# PCB-CMB-2.net
KiCad netlist of a schematic drawn in EAGLE
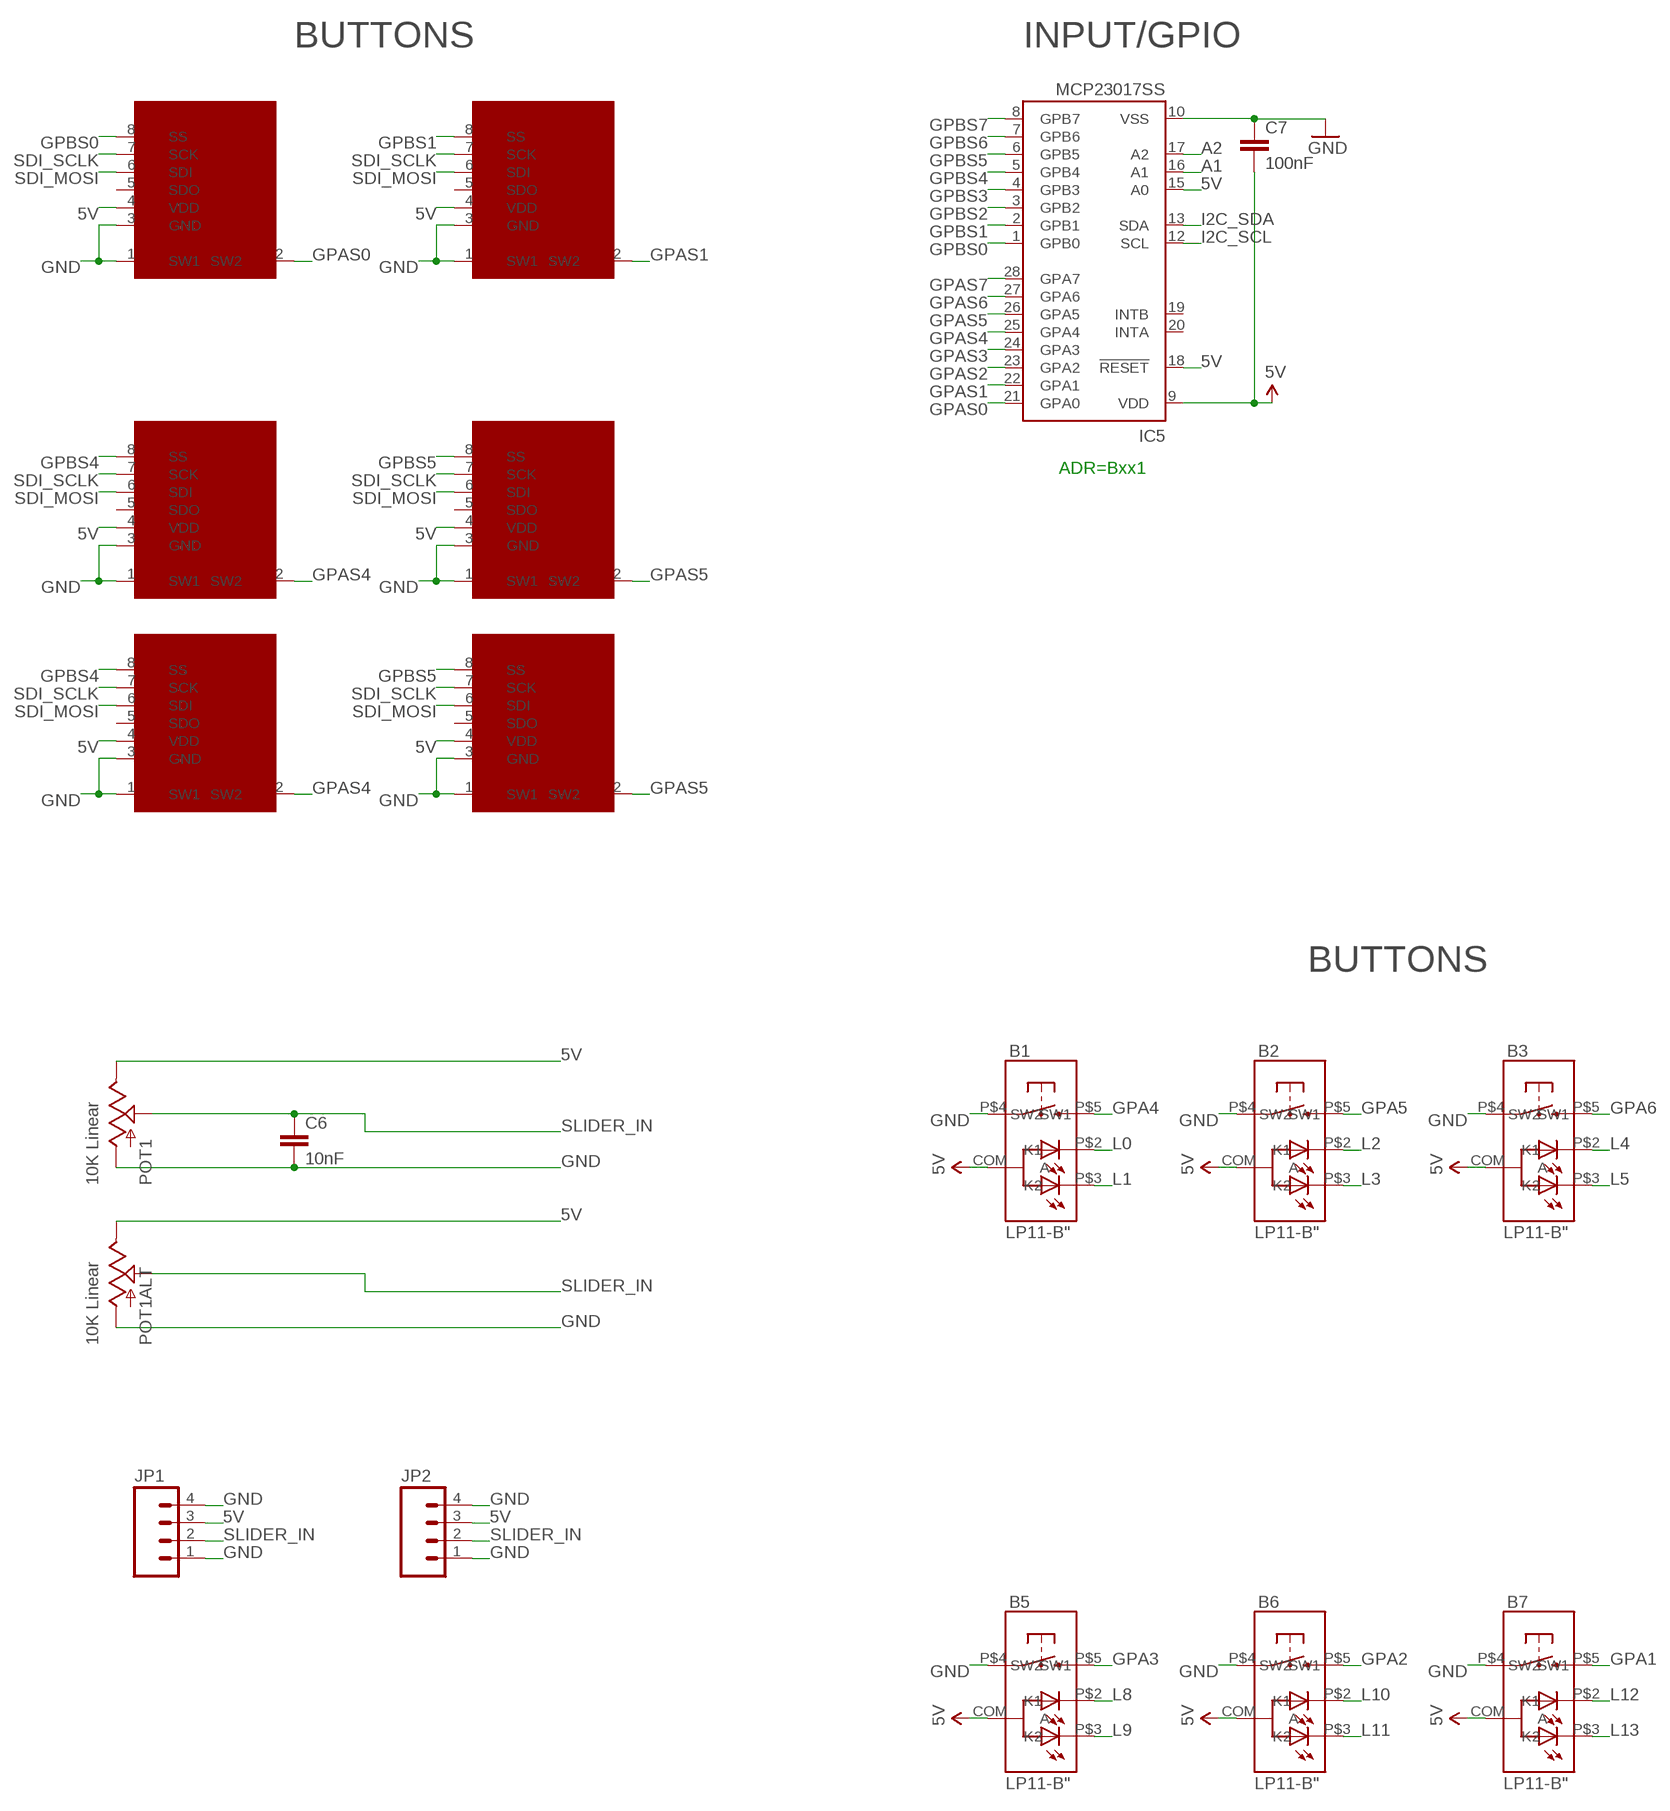
[diagram p0: schematic, sheet 1, part 1 of 2]
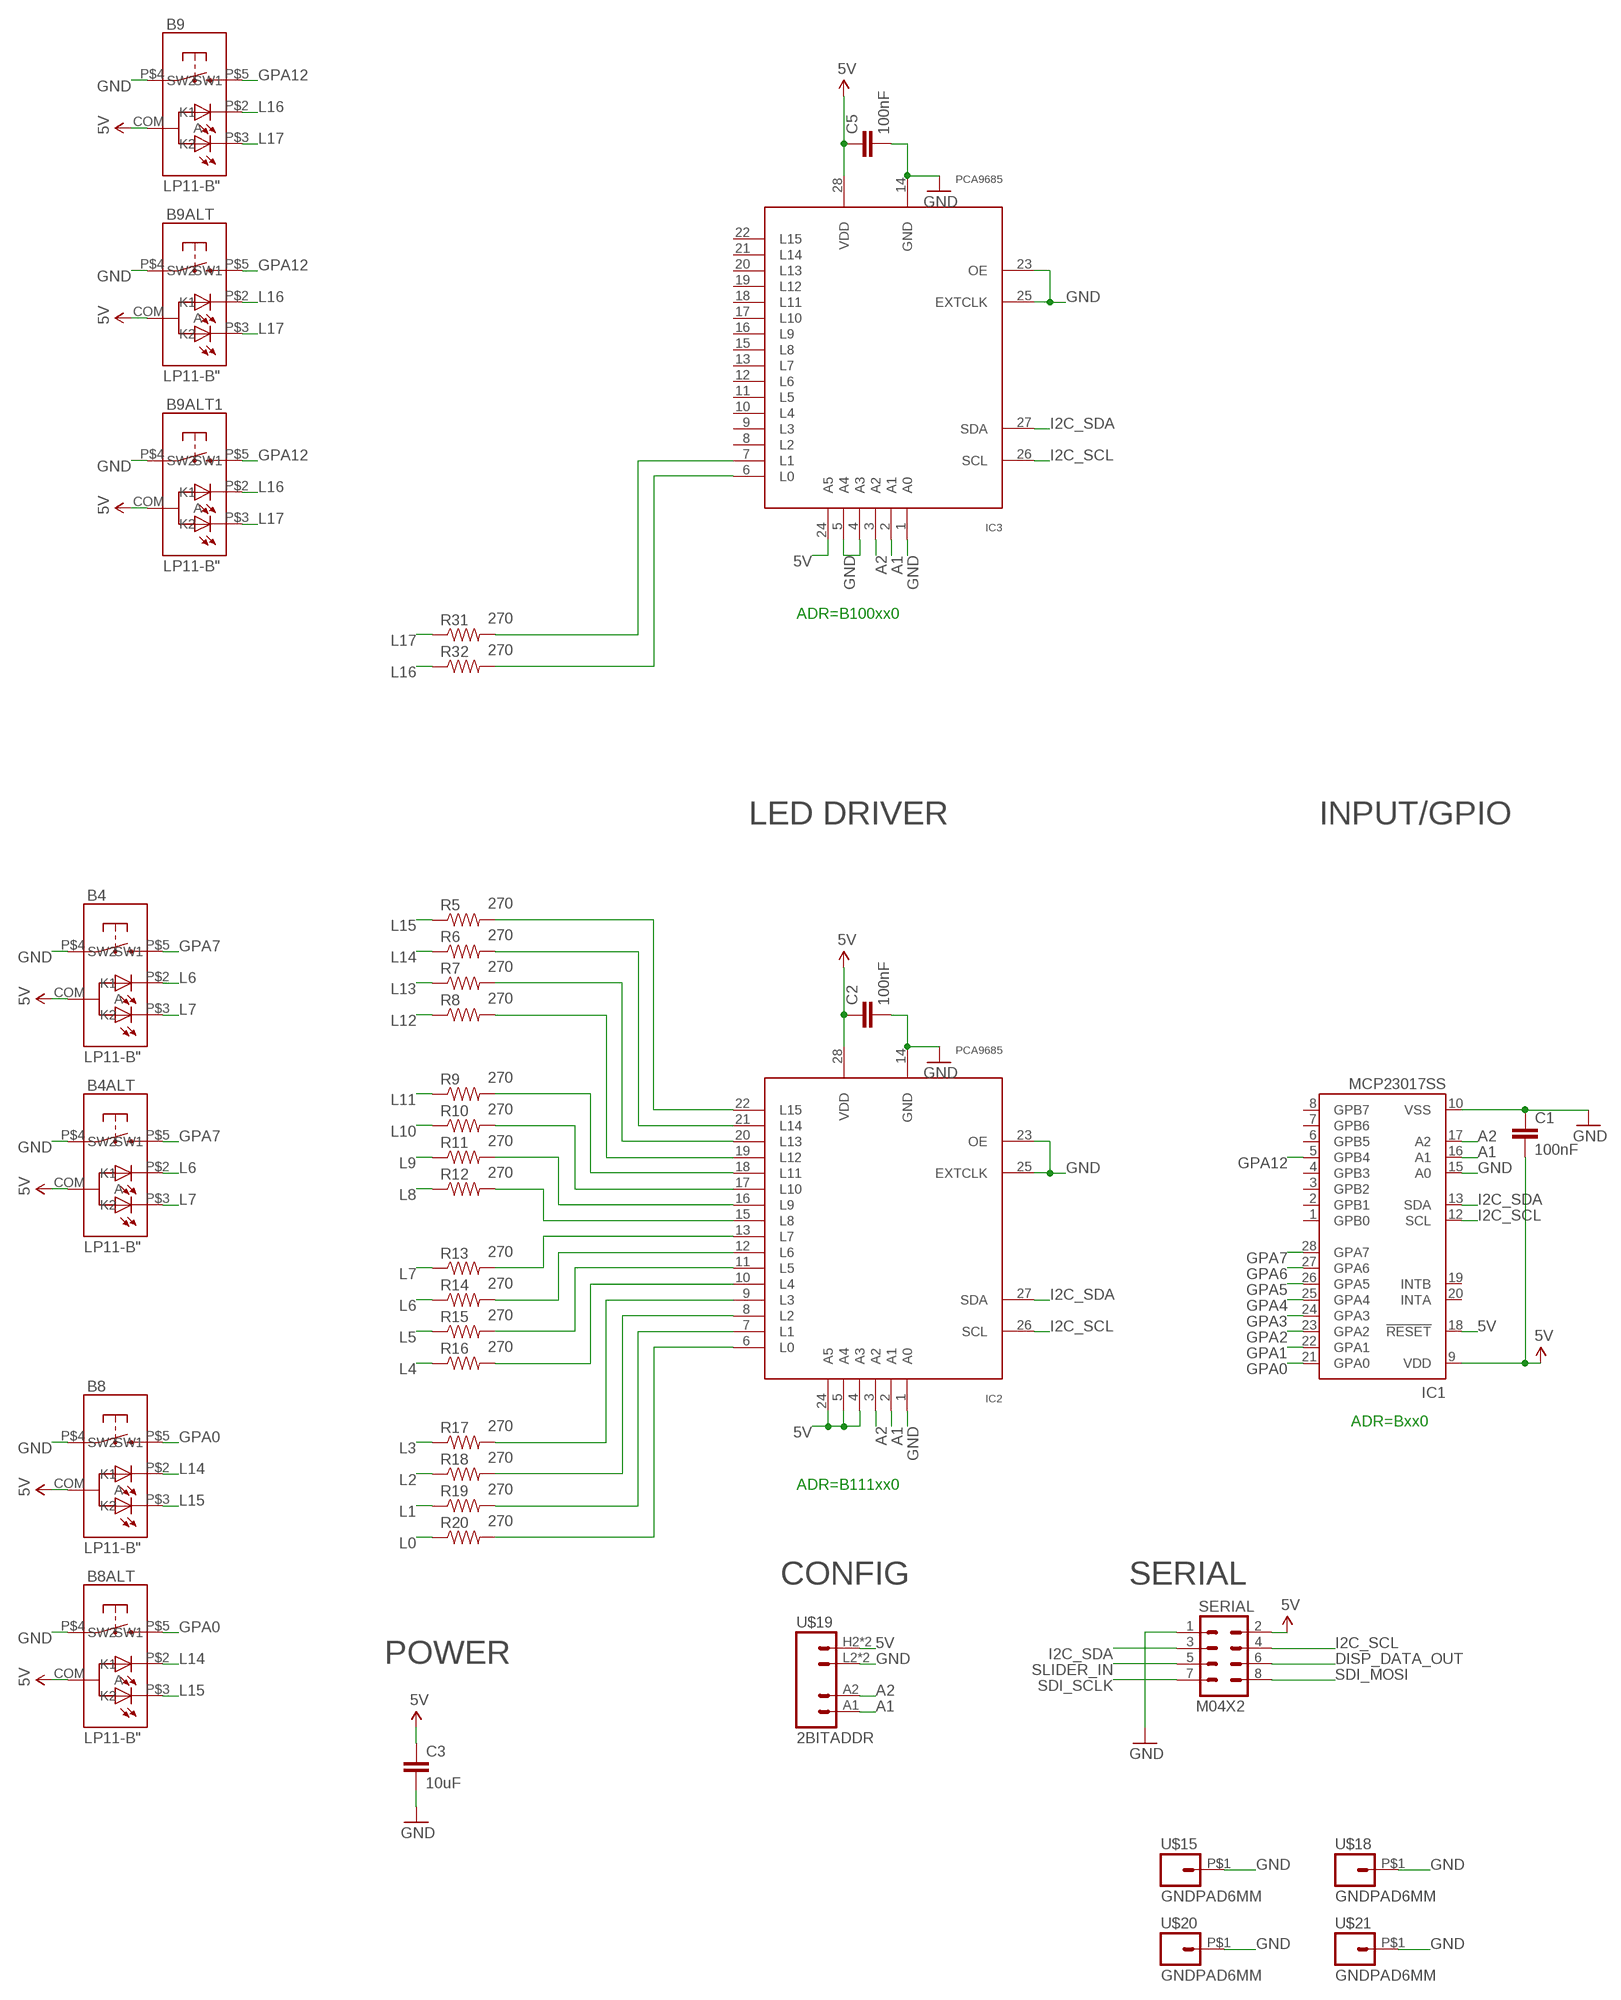
[diagram p1: schematic, sheet 1, part 2 of 2]

(export (version "E")
  (design (tool "Eeschema 10.0.6"))
  (components
    (comp (ref "B1")
      (value "LP11-B\"")
      (footprint "eagle-import:LP11")
      (libsource (lib "eagle-import") (part "LP11-B{dblquote}"))
    )
    (comp (ref "B2")
      (value "LP11-B\"")
      (footprint "eagle-import:LP11")
      (libsource (lib "eagle-import") (part "LP11-B{dblquote}"))
    )
    (comp (ref "B3")
      (value "LP11-B\"")
      (footprint "eagle-import:LP11")
      (libsource (lib "eagle-import") (part "LP11-B{dblquote}"))
    )
    (comp (ref "B4")
      (value "LP11-B\"")
      (footprint "eagle-import:LP11")
      (libsource (lib "eagle-import") (part "LP11-B{dblquote}"))
    )
    (comp (ref "B4ALT")
      (value "LP11-B\"")
      (footprint "eagle-import:LP11")
      (libsource (lib "eagle-import") (part "LP11-B{dblquote}"))
    )
    (comp (ref "B5")
      (value "LP11-B\"")
      (footprint "eagle-import:LP11")
      (libsource (lib "eagle-import") (part "LP11-B{dblquote}"))
    )
    (comp (ref "B6")
      (value "LP11-B\"")
      (footprint "eagle-import:LP11")
      (libsource (lib "eagle-import") (part "LP11-B{dblquote}"))
    )
    (comp (ref "B7")
      (value "LP11-B\"")
      (footprint "eagle-import:LP11")
      (libsource (lib "eagle-import") (part "LP11-B{dblquote}"))
    )
    (comp (ref "B8")
      (value "LP11-B\"")
      (footprint "eagle-import:LP11")
      (libsource (lib "eagle-import") (part "LP11-B{dblquote}"))
    )
    (comp (ref "B8ALT")
      (value "LP11-B\"")
      (footprint "eagle-import:LP11")
      (libsource (lib "eagle-import") (part "LP11-B{dblquote}"))
    )
    (comp (ref "B9")
      (value "LP11-B\"")
      (footprint "eagle-import:LP11")
      (libsource (lib "eagle-import") (part "LP11-B{dblquote}"))
    )
    (comp (ref "B9ALT")
      (value "LP11-B\"")
      (footprint "eagle-import:LP11")
      (libsource (lib "eagle-import") (part "LP11-B{dblquote}"))
    )
    (comp (ref "B9ALT1")
      (value "LP11-B\"")
      (footprint "eagle-import:LP11")
      (libsource (lib "eagle-import") (part "LP11-B{dblquote}"))
    )
    (comp (ref "C1")
      (value "100nF")
      (footprint "eagle-import:0603-CAP")
      (libsource (lib "eagle-import") (part "CAP0603-CAP"))
    )
    (comp (ref "C2")
      (value "100nF")
      (footprint "eagle-import:0603-CAP")
      (libsource (lib "eagle-import") (part "CAP0603-CAP"))
    )
    (comp (ref "C3")
      (value "10uF")
      (footprint "eagle-import:0805")
      (libsource (lib "eagle-import") (part "CAP0805"))
    )
    (comp (ref "C5")
      (value "100nF")
      (footprint "eagle-import:0603-CAP")
      (libsource (lib "eagle-import") (part "CAP0603-CAP"))
    )
    (comp (ref "C6")
      (value "10nF")
      (footprint "eagle-import:0603-CAP")
      (libsource (lib "eagle-import") (part "CAP0603-CAP"))
    )
    (comp (ref "C7")
      (value "100nF")
      (footprint "eagle-import:0603-CAP")
      (libsource (lib "eagle-import") (part "CAP0603-CAP"))
    )
    (comp (ref "IC1")
      (value "MCP23017SS")
      (footprint "eagle-import:SSOP28")
      (fields
        (field (name "MF") "MICROCHIP")
        (field (name "MPN") "MCP23017-E/SS")
        (field (name "MPN_1") "MCP23017-E/SS")
        (field (name "OC_FARNELL") "1467674")
        (field (name "OC_NEWARK") "31K2960")
      )
      (libsource (lib "eagle-import") (part "MCP23017SS"))
    )
    (comp (ref "IC2")
      (value "PCA9685")
      (footprint "eagle-import:TSSOP28")
      (libsource (lib "eagle-import") (part "PCA9685"))
    )
    (comp (ref "IC3")
      (value "PCA9685")
      (footprint "eagle-import:TSSOP28")
      (libsource (lib "eagle-import") (part "PCA9685"))
    )
    (comp (ref "IC5")
      (value "MCP23017SS")
      (footprint "eagle-import:SSOP28")
      (fields
        (field (name "MF") "MICROCHIP")
        (field (name "MPN") "MCP23017-E/SS")
        (field (name "MPN_1") "MCP23017-E/SS")
        (field (name "OC_FARNELL") "1467674")
        (field (name "OC_NEWARK") "31K2960")
      )
      (libsource (lib "eagle-import") (part "MCP23017SS"))
    )
    (comp (ref "JP1")
      (value "M04PTH")
      (footprint "eagle-import:1X04")
      (libsource (lib "eagle-import") (part "M04PTH"))
    )
    (comp (ref "JP2")
      (value "M04PTH")
      (footprint "eagle-import:1X04")
      (libsource (lib "eagle-import") (part "M04PTH"))
    )
    (comp (ref "POT1")
      (value "10K Linear")
      (footprint "eagle-import:SLIDER20")
      (libsource (lib "eagle-import") (part "SLIDER20"))
    )
    (comp (ref "POT1ALT")
      (value "10K Linear")
      (footprint "eagle-import:SLIDER20")
      (libsource (lib "eagle-import") (part "SLIDER20"))
    )
    (comp (ref "R5")
      (value "270")
      (footprint "eagle-import:0603-RES")
      (libsource (lib "eagle-import") (part "RESISTOR0603-RES"))
    )
    (comp (ref "R6")
      (value "270")
      (footprint "eagle-import:0603-RES")
      (libsource (lib "eagle-import") (part "RESISTOR0603-RES"))
    )
    (comp (ref "R7")
      (value "270")
      (footprint "eagle-import:0603-RES")
      (libsource (lib "eagle-import") (part "RESISTOR0603-RES"))
    )
    (comp (ref "R8")
      (value "270")
      (footprint "eagle-import:0603-RES")
      (libsource (lib "eagle-import") (part "RESISTOR0603-RES"))
    )
    (comp (ref "R9")
      (value "270")
      (footprint "eagle-import:0603-RES")
      (libsource (lib "eagle-import") (part "RESISTOR0603-RES"))
    )
    (comp (ref "R10")
      (value "270")
      (footprint "eagle-import:0603-RES")
      (libsource (lib "eagle-import") (part "RESISTOR0603-RES"))
    )
    (comp (ref "R11")
      (value "270")
      (footprint "eagle-import:0603-RES")
      (libsource (lib "eagle-import") (part "RESISTOR0603-RES"))
    )
    (comp (ref "R12")
      (value "270")
      (footprint "eagle-import:0603-RES")
      (libsource (lib "eagle-import") (part "RESISTOR0603-RES"))
    )
    (comp (ref "R13")
      (value "270")
      (footprint "eagle-import:0603-RES")
      (libsource (lib "eagle-import") (part "RESISTOR0603-RES"))
    )
    (comp (ref "R14")
      (value "270")
      (footprint "eagle-import:0603-RES")
      (libsource (lib "eagle-import") (part "RESISTOR0603-RES"))
    )
    (comp (ref "R15")
      (value "270")
      (footprint "eagle-import:0603-RES")
      (libsource (lib "eagle-import") (part "RESISTOR0603-RES"))
    )
    (comp (ref "R16")
      (value "270")
      (footprint "eagle-import:0603-RES")
      (libsource (lib "eagle-import") (part "RESISTOR0603-RES"))
    )
    (comp (ref "R17")
      (value "270")
      (footprint "eagle-import:0603-RES")
      (libsource (lib "eagle-import") (part "RESISTOR0603-RES"))
    )
    (comp (ref "R18")
      (value "270")
      (footprint "eagle-import:0603-RES")
      (libsource (lib "eagle-import") (part "RESISTOR0603-RES"))
    )
    (comp (ref "R19")
      (value "270")
      (footprint "eagle-import:0603-RES")
      (libsource (lib "eagle-import") (part "RESISTOR0603-RES"))
    )
    (comp (ref "R20")
      (value "270")
      (footprint "eagle-import:0603-RES")
      (libsource (lib "eagle-import") (part "RESISTOR0603-RES"))
    )
    (comp (ref "R31")
      (value "270")
      (footprint "eagle-import:0603-RES")
      (libsource (lib "eagle-import") (part "RESISTOR0603-RES"))
    )
    (comp (ref "R32")
      (value "270")
      (footprint "eagle-import:0603-RES")
      (libsource (lib "eagle-import") (part "RESISTOR0603-RES"))
    )
    (comp (ref "SERIAL")
      (value "M04X2")
      (footprint "eagle-import:2X4")
      (libsource (lib "eagle-import") (part "M04X2"))
    )
    (comp (ref "SSW1")
      (value "SMART_SWITCHSMART_SWITCH_8PIN")
      (footprint "eagle-import:SMART_SWITCH")
      (libsource (lib "eagle-import") (part "SMART_SWITCHSMART_SWITCH_8PIN"))
    )
    (comp (ref "SSW2")
      (value "SMART_SWITCHSMART_SWITCH_8PIN")
      (footprint "eagle-import:SMART_SWITCH")
      (libsource (lib "eagle-import") (part "SMART_SWITCHSMART_SWITCH_8PIN"))
    )
    (comp (ref "SSW5")
      (value "SMART_SWITCHSMART_SWITCH_8PIN")
      (footprint "eagle-import:SMART_SWITCH")
      (libsource (lib "eagle-import") (part "SMART_SWITCHSMART_SWITCH_8PIN"))
    )
    (comp (ref "SSW5ALT")
      (value "SMART_SWITCHSMART_SWITCH_8PIN")
      (footprint "eagle-import:SMART_SWITCH")
      (libsource (lib "eagle-import") (part "SMART_SWITCHSMART_SWITCH_8PIN"))
    )
    (comp (ref "SSW6")
      (value "SMART_SWITCHSMART_SWITCH_8PIN")
      (footprint "eagle-import:SMART_SWITCH")
      (libsource (lib "eagle-import") (part "SMART_SWITCHSMART_SWITCH_8PIN"))
    )
    (comp (ref "SSW6ALT")
      (value "SMART_SWITCHSMART_SWITCH_8PIN")
      (footprint "eagle-import:SMART_SWITCH")
      (libsource (lib "eagle-import") (part "SMART_SWITCHSMART_SWITCH_8PIN"))
    )
    (comp (ref "U$15")
      (value "GNDPAD6MM")
      (footprint "eagle-import:3.2MMPAD6MM")
      (libsource (lib "eagle-import") (part "GNDPAD6MM"))
    )
    (comp (ref "U$18")
      (value "GNDPAD6MM")
      (footprint "eagle-import:3.2MMPAD6MM")
      (libsource (lib "eagle-import") (part "GNDPAD6MM"))
    )
    (comp (ref "U$19")
      (value "2BITADDR")
      (footprint "eagle-import:2BITADDR")
      (libsource (lib "eagle-import") (part "2BITADDR"))
    )
    (comp (ref "U$20")
      (value "GNDPAD6MM")
      (footprint "eagle-import:3.2MMPAD6MM")
      (libsource (lib "eagle-import") (part "GNDPAD6MM"))
    )
    (comp (ref "U$21")
      (value "GNDPAD6MM")
      (footprint "eagle-import:3.2MMPAD6MM")
      (libsource (lib "eagle-import") (part "GNDPAD6MM"))
    )
  )
  (nets
    (net (code "1") (name "5V") (class "Default")
      (node (ref "B1") (pin "COM") (pinfunction "A_COM") (pintype "bidirectional"))
      (node (ref "B2") (pin "COM") (pinfunction "A_COM") (pintype "bidirectional"))
      (node (ref "B3") (pin "COM") (pinfunction "A_COM") (pintype "bidirectional"))
      (node (ref "B4") (pin "COM") (pinfunction "A_COM") (pintype "bidirectional"))
      (node (ref "B4ALT") (pin "COM") (pinfunction "A_COM") (pintype "bidirectional"))
      (node (ref "B5") (pin "COM") (pinfunction "A_COM") (pintype "bidirectional"))
      (node (ref "B6") (pin "COM") (pinfunction "A_COM") (pintype "bidirectional"))
      (node (ref "B7") (pin "COM") (pinfunction "A_COM") (pintype "bidirectional"))
      (node (ref "B8") (pin "COM") (pinfunction "A_COM") (pintype "bidirectional"))
      (node (ref "B8ALT") (pin "COM") (pinfunction "A_COM") (pintype "bidirectional"))
      (node (ref "B9") (pin "COM") (pinfunction "A_COM") (pintype "bidirectional"))
      (node (ref "B9ALT") (pin "COM") (pinfunction "A_COM") (pintype "bidirectional"))
      (node (ref "B9ALT1") (pin "COM") (pinfunction "A_COM") (pintype "bidirectional"))
      (node (ref "C1") (pin "2") (pinfunction "2_2") (pintype "passive"))
      (node (ref "C2") (pin "1") (pinfunction "1_1") (pintype "passive"))
      (node (ref "C3") (pin "1") (pinfunction "1_1") (pintype "passive"))
      (node (ref "C5") (pin "1") (pinfunction "1_1") (pintype "passive"))
      (node (ref "C7") (pin "2") (pinfunction "2_2") (pintype "passive"))
      (node (ref "IC1") (pin "18") (pinfunction "~{RESET}_18") (pintype "input"))
      (node (ref "IC1") (pin "9") (pinfunction "VDD_9") (pintype "power_in"))
      (node (ref "IC2") (pin "24") (pinfunction "A5_24") (pintype "input"))
      (node (ref "IC2") (pin "28") (pinfunction "VDD_28") (pintype "power_in"))
      (node (ref "IC2") (pin "4") (pinfunction "A3_4") (pintype "input"))
      (node (ref "IC2") (pin "5") (pinfunction "A4_5") (pintype "input"))
      (node (ref "IC3") (pin "24") (pinfunction "A5_24") (pintype "input"))
      (node (ref "IC3") (pin "28") (pinfunction "VDD_28") (pintype "power_in"))
      (node (ref "IC5") (pin "15") (pinfunction "A0_15") (pintype "input"))
      (node (ref "IC5") (pin "18") (pinfunction "~{RESET}_18") (pintype "input"))
      (node (ref "IC5") (pin "9") (pinfunction "VDD_9") (pintype "power_in"))
      (node (ref "JP1") (pin "3") (pinfunction "3_3") (pintype "passive"))
      (node (ref "JP2") (pin "3") (pinfunction "3_3") (pintype "passive"))
      (node (ref "POT1") (pin "1") (pinfunction "E_1") (pintype "passive"))
      (node (ref "POT1ALT") (pin "1") (pinfunction "E_1") (pintype "passive"))
      (node (ref "SERIAL") (pin "2") (pinfunction "2_2") (pintype "passive"))
      (node (ref "SSW1") (pin "4") (pinfunction "VDD_4") (pintype "bidirectional"))
      (node (ref "SSW2") (pin "4") (pinfunction "VDD_4") (pintype "bidirectional"))
      (node (ref "SSW5") (pin "4") (pinfunction "VDD_4") (pintype "bidirectional"))
      (node (ref "SSW5ALT") (pin "4") (pinfunction "VDD_4") (pintype "bidirectional"))
      (node (ref "SSW6") (pin "4") (pinfunction "VDD_4") (pintype "bidirectional"))
      (node (ref "SSW6ALT") (pin "4") (pinfunction "VDD_4") (pintype "bidirectional"))
      (node (ref "U$19") (pin "H2") (pinfunction "VCC_H2") (pintype "passive"))
      (node (ref "U$19") (pin "H3") (pinfunction "VCC_H3") (pintype "passive"))
    )
    (net (code "2") (name "A1") (class "Default")
      (node (ref "IC1") (pin "16") (pinfunction "A1_16") (pintype "input"))
      (node (ref "IC2") (pin "2") (pinfunction "A1_2") (pintype "input"))
      (node (ref "IC3") (pin "2") (pinfunction "A1_2") (pintype "input"))
      (node (ref "IC5") (pin "16") (pinfunction "A1_16") (pintype "input"))
      (node (ref "U$19") (pin "A1") (pinfunction "A1_A1") (pintype "passive"))
    )
    (net (code "3") (name "A2") (class "Default")
      (node (ref "IC1") (pin "17") (pinfunction "A2_17") (pintype "input"))
      (node (ref "IC2") (pin "3") (pinfunction "A2_3") (pintype "input"))
      (node (ref "IC3") (pin "3") (pinfunction "A2_3") (pintype "input"))
      (node (ref "IC5") (pin "17") (pinfunction "A2_17") (pintype "input"))
      (node (ref "U$19") (pin "A2") (pinfunction "A2_A2") (pintype "passive"))
    )
    (net (code "4") (name "DISP_DATA_OUT") (class "Default")
      (node (ref "SERIAL") (pin "6") (pinfunction "6_6") (pintype "passive"))
    )
    (net (code "5") (name "GND") (class "Default")
      (node (ref "B1") (pin "P$4") (pinfunction "SW1_P$4") (pintype "bidirectional"))
      (node (ref "B2") (pin "P$4") (pinfunction "SW1_P$4") (pintype "bidirectional"))
      (node (ref "B3") (pin "P$4") (pinfunction "SW1_P$4") (pintype "bidirectional"))
      (node (ref "B4") (pin "P$4") (pinfunction "SW1_P$4") (pintype "bidirectional"))
      (node (ref "B4ALT") (pin "P$4") (pinfunction "SW1_P$4") (pintype "bidirectional"))
      (node (ref "B5") (pin "P$4") (pinfunction "SW1_P$4") (pintype "bidirectional"))
      (node (ref "B6") (pin "P$4") (pinfunction "SW1_P$4") (pintype "bidirectional"))
      (node (ref "B7") (pin "P$4") (pinfunction "SW1_P$4") (pintype "bidirectional"))
      (node (ref "B8") (pin "P$4") (pinfunction "SW1_P$4") (pintype "bidirectional"))
      (node (ref "B8ALT") (pin "P$4") (pinfunction "SW1_P$4") (pintype "bidirectional"))
      (node (ref "B9") (pin "P$4") (pinfunction "SW1_P$4") (pintype "bidirectional"))
      (node (ref "B9ALT") (pin "P$4") (pinfunction "SW1_P$4") (pintype "bidirectional"))
      (node (ref "B9ALT1") (pin "P$4") (pinfunction "SW1_P$4") (pintype "bidirectional"))
      (node (ref "C1") (pin "1") (pinfunction "1_1") (pintype "passive"))
      (node (ref "C2") (pin "2") (pinfunction "2_2") (pintype "passive"))
      (node (ref "C3") (pin "2") (pinfunction "2_2") (pintype "passive"))
      (node (ref "C5") (pin "2") (pinfunction "2_2") (pintype "passive"))
      (node (ref "C6") (pin "2") (pinfunction "2_2") (pintype "passive"))
      (node (ref "C7") (pin "1") (pinfunction "1_1") (pintype "passive"))
      (node (ref "IC1") (pin "10") (pinfunction "VSS_10") (pintype "power_in"))
      (node (ref "IC1") (pin "15") (pinfunction "A0_15") (pintype "input"))
      (node (ref "IC2") (pin "1") (pinfunction "A0_1") (pintype "input"))
      (node (ref "IC2") (pin "14") (pinfunction "GND_14") (pintype "power_in"))
      (node (ref "IC2") (pin "23") (pinfunction "OE_23") (pintype "input"))
      (node (ref "IC2") (pin "25") (pinfunction "EXTCLK_25") (pintype "input"))
      (node (ref "IC3") (pin "1") (pinfunction "A0_1") (pintype "input"))
      (node (ref "IC3") (pin "14") (pinfunction "GND_14") (pintype "power_in"))
      (node (ref "IC3") (pin "23") (pinfunction "OE_23") (pintype "input"))
      (node (ref "IC3") (pin "25") (pinfunction "EXTCLK_25") (pintype "input"))
      (node (ref "IC3") (pin "4") (pinfunction "A3_4") (pintype "input"))
      (node (ref "IC3") (pin "5") (pinfunction "A4_5") (pintype "input"))
      (node (ref "IC5") (pin "10") (pinfunction "VSS_10") (pintype "power_in"))
      (node (ref "JP1") (pin "1") (pinfunction "1_1") (pintype "passive"))
      (node (ref "JP1") (pin "4") (pinfunction "4_4") (pintype "passive"))
      (node (ref "JP2") (pin "1") (pinfunction "1_1") (pintype "passive"))
      (node (ref "JP2") (pin "4") (pinfunction "4_4") (pintype "passive"))
      (node (ref "POT1") (pin "3") (pinfunction "A_3") (pintype "passive"))
      (node (ref "POT1ALT") (pin "3") (pinfunction "A_3") (pintype "passive"))
      (node (ref "SERIAL") (pin "1") (pinfunction "1_1") (pintype "passive"))
      (node (ref "SSW1") (pin "1") (pinfunction "SW1_1") (pintype "bidirectional"))
      (node (ref "SSW1") (pin "3") (pinfunction "GND_3") (pintype "bidirectional"))
      (node (ref "SSW2") (pin "1") (pinfunction "SW1_1") (pintype "bidirectional"))
      (node (ref "SSW2") (pin "3") (pinfunction "GND_3") (pintype "bidirectional"))
      (node (ref "SSW5") (pin "1") (pinfunction "SW1_1") (pintype "bidirectional"))
      (node (ref "SSW5") (pin "3") (pinfunction "GND_3") (pintype "bidirectional"))
      (node (ref "SSW5ALT") (pin "1") (pinfunction "SW1_1") (pintype "bidirectional"))
      (node (ref "SSW5ALT") (pin "3") (pinfunction "GND_3") (pintype "bidirectional"))
      (node (ref "SSW6") (pin "1") (pinfunction "SW1_1") (pintype "bidirectional"))
      (node (ref "SSW6") (pin "3") (pinfunction "GND_3") (pintype "bidirectional"))
      (node (ref "SSW6ALT") (pin "1") (pinfunction "SW1_1") (pintype "bidirectional"))
      (node (ref "SSW6ALT") (pin "3") (pinfunction "GND_3") (pintype "bidirectional"))
      (node (ref "U$15") (pin "P$1") (pinfunction "1_P$1") (pintype "passive"))
      (node (ref "U$18") (pin "P$1") (pinfunction "1_P$1") (pintype "passive"))
      (node (ref "U$19") (pin "L2") (pinfunction "GND_L2") (pintype "passive"))
      (node (ref "U$19") (pin "L3") (pinfunction "GND_L3") (pintype "passive"))
      (node (ref "U$20") (pin "P$1") (pinfunction "1_P$1") (pintype "passive"))
      (node (ref "U$21") (pin "P$1") (pinfunction "1_P$1") (pintype "passive"))
    )
    (net (code "6") (name "GPA0") (class "Default")
      (node (ref "B8") (pin "P$5") (pinfunction "SW2_P$5") (pintype "bidirectional"))
      (node (ref "B8ALT") (pin "P$5") (pinfunction "SW2_P$5") (pintype "bidirectional"))
      (node (ref "IC1") (pin "21") (pinfunction "GPA0_21") (pintype "bidirectional"))
    )
    (net (code "7") (name "GPA1") (class "Default")
      (node (ref "B7") (pin "P$5") (pinfunction "SW2_P$5") (pintype "bidirectional"))
      (node (ref "IC1") (pin "22") (pinfunction "GPA1_22") (pintype "bidirectional"))
    )
    (net (code "8") (name "GPA2") (class "Default")
      (node (ref "B6") (pin "P$5") (pinfunction "SW2_P$5") (pintype "bidirectional"))
      (node (ref "IC1") (pin "23") (pinfunction "GPA2_23") (pintype "bidirectional"))
    )
    (net (code "9") (name "GPA3") (class "Default")
      (node (ref "B5") (pin "P$5") (pinfunction "SW2_P$5") (pintype "bidirectional"))
      (node (ref "IC1") (pin "24") (pinfunction "GPA3_24") (pintype "bidirectional"))
    )
    (net (code "10") (name "GPA4") (class "Default")
      (node (ref "B1") (pin "P$5") (pinfunction "SW2_P$5") (pintype "bidirectional"))
      (node (ref "IC1") (pin "25") (pinfunction "GPA4_25") (pintype "bidirectional"))
    )
    (net (code "11") (name "GPA5") (class "Default")
      (node (ref "B2") (pin "P$5") (pinfunction "SW2_P$5") (pintype "bidirectional"))
      (node (ref "IC1") (pin "26") (pinfunction "GPA5_26") (pintype "bidirectional"))
    )
    (net (code "12") (name "GPA6") (class "Default")
      (node (ref "B3") (pin "P$5") (pinfunction "SW2_P$5") (pintype "bidirectional"))
      (node (ref "IC1") (pin "27") (pinfunction "GPA6_27") (pintype "bidirectional"))
    )
    (net (code "13") (name "GPA7") (class "Default")
      (node (ref "B4") (pin "P$5") (pinfunction "SW2_P$5") (pintype "bidirectional"))
      (node (ref "B4ALT") (pin "P$5") (pinfunction "SW2_P$5") (pintype "bidirectional"))
      (node (ref "IC1") (pin "28") (pinfunction "GPA7_28") (pintype "bidirectional"))
    )
    (net (code "14") (name "GPA12") (class "Default")
      (node (ref "B9") (pin "P$5") (pinfunction "SW2_P$5") (pintype "bidirectional"))
      (node (ref "B9ALT") (pin "P$5") (pinfunction "SW2_P$5") (pintype "bidirectional"))
      (node (ref "B9ALT1") (pin "P$5") (pinfunction "SW2_P$5") (pintype "bidirectional"))
      (node (ref "IC1") (pin "5") (pinfunction "GPB4_5") (pintype "bidirectional"))
    )
    (net (code "15") (name "GPAS0") (class "Default")
      (node (ref "IC5") (pin "21") (pinfunction "GPA0_21") (pintype "bidirectional"))
      (node (ref "SSW1") (pin "2") (pinfunction "SW2_2") (pintype "bidirectional"))
    )
    (net (code "16") (name "GPAS1") (class "Default")
      (node (ref "IC5") (pin "22") (pinfunction "GPA1_22") (pintype "bidirectional"))
      (node (ref "SSW2") (pin "2") (pinfunction "SW2_2") (pintype "bidirectional"))
    )
    (net (code "17") (name "GPAS2") (class "Default")
      (node (ref "IC5") (pin "23") (pinfunction "GPA2_23") (pintype "bidirectional"))
    )
    (net (code "18") (name "GPAS3") (class "Default")
      (node (ref "IC5") (pin "24") (pinfunction "GPA3_24") (pintype "bidirectional"))
    )
    (net (code "19") (name "GPAS4") (class "Default")
      (node (ref "IC5") (pin "25") (pinfunction "GPA4_25") (pintype "bidirectional"))
      (node (ref "SSW5") (pin "2") (pinfunction "SW2_2") (pintype "bidirectional"))
      (node (ref "SSW5ALT") (pin "2") (pinfunction "SW2_2") (pintype "bidirectional"))
    )
    (net (code "20") (name "GPAS5") (class "Default")
      (node (ref "IC5") (pin "26") (pinfunction "GPA5_26") (pintype "bidirectional"))
      (node (ref "SSW6") (pin "2") (pinfunction "SW2_2") (pintype "bidirectional"))
      (node (ref "SSW6ALT") (pin "2") (pinfunction "SW2_2") (pintype "bidirectional"))
    )
    (net (code "21") (name "GPAS6") (class "Default")
      (node (ref "IC5") (pin "27") (pinfunction "GPA6_27") (pintype "bidirectional"))
    )
    (net (code "22") (name "GPAS7") (class "Default")
      (node (ref "IC5") (pin "28") (pinfunction "GPA7_28") (pintype "bidirectional"))
    )
    (net (code "23") (name "GPBS0") (class "Default")
      (node (ref "IC5") (pin "1") (pinfunction "GPB0_1") (pintype "bidirectional"))
      (node (ref "SSW1") (pin "8") (pinfunction "SS_8") (pintype "bidirectional"))
    )
    (net (code "24") (name "GPBS1") (class "Default")
      (node (ref "IC5") (pin "2") (pinfunction "GPB1_2") (pintype "bidirectional"))
      (node (ref "SSW2") (pin "8") (pinfunction "SS_8") (pintype "bidirectional"))
    )
    (net (code "25") (name "GPBS2") (class "Default")
      (node (ref "IC5") (pin "3") (pinfunction "GPB2_3") (pintype "bidirectional"))
    )
    (net (code "26") (name "GPBS3") (class "Default")
      (node (ref "IC5") (pin "4") (pinfunction "GPB3_4") (pintype "bidirectional"))
    )
    (net (code "27") (name "GPBS4") (class "Default")
      (node (ref "IC5") (pin "5") (pinfunction "GPB4_5") (pintype "bidirectional"))
      (node (ref "SSW5") (pin "8") (pinfunction "SS_8") (pintype "bidirectional"))
      (node (ref "SSW5ALT") (pin "8") (pinfunction "SS_8") (pintype "bidirectional"))
    )
    (net (code "28") (name "GPBS5") (class "Default")
      (node (ref "IC5") (pin "6") (pinfunction "GPB5_6") (pintype "bidirectional"))
      (node (ref "SSW6") (pin "8") (pinfunction "SS_8") (pintype "bidirectional"))
      (node (ref "SSW6ALT") (pin "8") (pinfunction "SS_8") (pintype "bidirectional"))
    )
    (net (code "29") (name "GPBS6") (class "Default")
      (node (ref "IC5") (pin "7") (pinfunction "GPB6_7") (pintype "bidirectional"))
    )
    (net (code "30") (name "GPBS7") (class "Default")
      (node (ref "IC5") (pin "8") (pinfunction "GPB7_8") (pintype "bidirectional"))
    )
    (net (code "31") (name "I2C_SCL") (class "Default")
      (node (ref "IC1") (pin "12") (pinfunction "SCL_12") (pintype "input"))
      (node (ref "IC2") (pin "26") (pinfunction "SCL_26") (pintype "input"))
      (node (ref "IC3") (pin "26") (pinfunction "SCL_26") (pintype "input"))
      (node (ref "IC5") (pin "12") (pinfunction "SCL_12") (pintype "input"))
      (node (ref "SERIAL") (pin "4") (pinfunction "4_4") (pintype "passive"))
    )
    (net (code "32") (name "I2C_SDA") (class "Default")
      (node (ref "IC1") (pin "13") (pinfunction "SDA_13") (pintype "bidirectional"))
      (node (ref "IC2") (pin "27") (pinfunction "SDA_27") (pintype "input"))
      (node (ref "IC3") (pin "27") (pinfunction "SDA_27") (pintype "input"))
      (node (ref "IC5") (pin "13") (pinfunction "SDA_13") (pintype "bidirectional"))
      (node (ref "SERIAL") (pin "3") (pinfunction "3_3") (pintype "passive"))
    )
    (net (code "33") (name "L0") (class "Default")
      (node (ref "B1") (pin "P$2") (pinfunction "K1_P$2") (pintype "bidirectional"))
      (node (ref "R20") (pin "1") (pinfunction "1_1") (pintype "passive"))
    )
    (net (code "34") (name "L1") (class "Default")
      (node (ref "B1") (pin "P$3") (pinfunction "K2_P$3") (pintype "bidirectional"))
      (node (ref "R19") (pin "1") (pinfunction "1_1") (pintype "passive"))
    )
    (net (code "35") (name "L2") (class "Default")
      (node (ref "B2") (pin "P$2") (pinfunction "K1_P$2") (pintype "bidirectional"))
      (node (ref "R18") (pin "1") (pinfunction "1_1") (pintype "passive"))
    )
    (net (code "36") (name "L3") (class "Default")
      (node (ref "B2") (pin "P$3") (pinfunction "K2_P$3") (pintype "bidirectional"))
      (node (ref "R17") (pin "1") (pinfunction "1_1") (pintype "passive"))
    )
    (net (code "37") (name "L4") (class "Default")
      (node (ref "B3") (pin "P$2") (pinfunction "K1_P$2") (pintype "bidirectional"))
      (node (ref "R16") (pin "1") (pinfunction "1_1") (pintype "passive"))
    )
    (net (code "38") (name "L5") (class "Default")
      (node (ref "B3") (pin "P$3") (pinfunction "K2_P$3") (pintype "bidirectional"))
      (node (ref "R15") (pin "1") (pinfunction "1_1") (pintype "passive"))
    )
    (net (code "39") (name "L6") (class "Default")
      (node (ref "B4") (pin "P$2") (pinfunction "K1_P$2") (pintype "bidirectional"))
      (node (ref "B4ALT") (pin "P$2") (pinfunction "K1_P$2") (pintype "bidirectional"))
      (node (ref "R14") (pin "1") (pinfunction "1_1") (pintype "passive"))
    )
    (net (code "40") (name "L7") (class "Default")
      (node (ref "B4") (pin "P$3") (pinfunction "K2_P$3") (pintype "bidirectional"))
      (node (ref "B4ALT") (pin "P$3") (pinfunction "K2_P$3") (pintype "bidirectional"))
      (node (ref "R13") (pin "1") (pinfunction "1_1") (pintype "passive"))
    )
    (net (code "41") (name "L8") (class "Default")
      (node (ref "B5") (pin "P$2") (pinfunction "K1_P$2") (pintype "bidirectional"))
      (node (ref "R12") (pin "1") (pinfunction "1_1") (pintype "passive"))
    )
    (net (code "42") (name "L9") (class "Default")
      (node (ref "B5") (pin "P$3") (pinfunction "K2_P$3") (pintype "bidirectional"))
      (node (ref "R11") (pin "1") (pinfunction "1_1") (pintype "passive"))
    )
    (net (code "43") (name "L10") (class "Default")
      (node (ref "B6") (pin "P$2") (pinfunction "K1_P$2") (pintype "bidirectional"))
      (node (ref "R10") (pin "1") (pinfunction "1_1") (pintype "passive"))
    )
    (net (code "44") (name "L11") (class "Default")
      (node (ref "B6") (pin "P$3") (pinfunction "K2_P$3") (pintype "bidirectional"))
      (node (ref "R9") (pin "1") (pinfunction "1_1") (pintype "passive"))
    )
    (net (code "45") (name "L12") (class "Default")
      (node (ref "B7") (pin "P$2") (pinfunction "K1_P$2") (pintype "bidirectional"))
      (node (ref "R8") (pin "1") (pinfunction "1_1") (pintype "passive"))
    )
    (net (code "46") (name "L13") (class "Default")
      (node (ref "B7") (pin "P$3") (pinfunction "K2_P$3") (pintype "bidirectional"))
      (node (ref "R7") (pin "1") (pinfunction "1_1") (pintype "passive"))
    )
    (net (code "47") (name "L14") (class "Default")
      (node (ref "B8") (pin "P$2") (pinfunction "K1_P$2") (pintype "bidirectional"))
      (node (ref "B8ALT") (pin "P$2") (pinfunction "K1_P$2") (pintype "bidirectional"))
      (node (ref "R6") (pin "1") (pinfunction "1_1") (pintype "passive"))
    )
    (net (code "48") (name "L15") (class "Default")
      (node (ref "B8") (pin "P$3") (pinfunction "K2_P$3") (pintype "bidirectional"))
      (node (ref "B8ALT") (pin "P$3") (pinfunction "K2_P$3") (pintype "bidirectional"))
      (node (ref "R5") (pin "1") (pinfunction "1_1") (pintype "passive"))
    )
    (net (code "49") (name "L16") (class "Default")
      (node (ref "B9") (pin "P$2") (pinfunction "K1_P$2") (pintype "bidirectional"))
      (node (ref "B9ALT") (pin "P$2") (pinfunction "K1_P$2") (pintype "bidirectional"))
      (node (ref "B9ALT1") (pin "P$2") (pinfunction "K1_P$2") (pintype "bidirectional"))
      (node (ref "R32") (pin "1") (pinfunction "1_1") (pintype "passive"))
    )
    (net (code "50") (name "L17") (class "Default")
      (node (ref "B9") (pin "P$3") (pinfunction "K2_P$3") (pintype "bidirectional"))
      (node (ref "B9ALT") (pin "P$3") (pinfunction "K2_P$3") (pintype "bidirectional"))
      (node (ref "B9ALT1") (pin "P$3") (pinfunction "K2_P$3") (pintype "bidirectional"))
      (node (ref "R31") (pin "1") (pinfunction "1_1") (pintype "passive"))
    )
    (net (code "51") (name "Net-(IC2-L0)") (class "Default")
      (node (ref "IC2") (pin "6") (pinfunction "L0_6") (pintype "output"))
      (node (ref "R20") (pin "2") (pinfunction "2_2") (pintype "passive"))
    )
    (net (code "52") (name "Net-(IC2-L1)") (class "Default")
      (node (ref "IC2") (pin "7") (pinfunction "L1_7") (pintype "output"))
      (node (ref "R19") (pin "2") (pinfunction "2_2") (pintype "passive"))
    )
    (net (code "53") (name "Net-(IC2-L2)") (class "Default")
      (node (ref "IC2") (pin "8") (pinfunction "L2_8") (pintype "output"))
      (node (ref "R18") (pin "2") (pinfunction "2_2") (pintype "passive"))
    )
    (net (code "54") (name "Net-(IC2-L3)") (class "Default")
      (node (ref "IC2") (pin "9") (pinfunction "L3_9") (pintype "output"))
      (node (ref "R17") (pin "2") (pinfunction "2_2") (pintype "passive"))
    )
    (net (code "55") (name "Net-(IC2-L4)") (class "Default")
      (node (ref "IC2") (pin "10") (pinfunction "L4_10") (pintype "output"))
      (node (ref "R16") (pin "2") (pinfunction "2_2") (pintype "passive"))
    )
    (net (code "56") (name "Net-(IC2-L5)") (class "Default")
      (node (ref "IC2") (pin "11") (pinfunction "L5_11") (pintype "output"))
      (node (ref "R15") (pin "2") (pinfunction "2_2") (pintype "passive"))
    )
    (net (code "57") (name "Net-(IC2-L6)") (class "Default")
      (node (ref "IC2") (pin "12") (pinfunction "L6_12") (pintype "output"))
      (node (ref "R14") (pin "2") (pinfunction "2_2") (pintype "passive"))
    )
    (net (code "58") (name "Net-(IC2-L7)") (class "Default")
      (node (ref "IC2") (pin "13") (pinfunction "L7_13") (pintype "output"))
      (node (ref "R13") (pin "2") (pinfunction "2_2") (pintype "passive"))
    )
    (net (code "59") (name "Net-(IC2-L8)") (class "Default")
      (node (ref "IC2") (pin "15") (pinfunction "L8_15") (pintype "output"))
      (node (ref "R12") (pin "2") (pinfunction "2_2") (pintype "passive"))
    )
    (net (code "60") (name "Net-(IC2-L9)") (class "Default")
      (node (ref "IC2") (pin "16") (pinfunction "L9_16") (pintype "output"))
      (node (ref "R11") (pin "2") (pinfunction "2_2") (pintype "passive"))
    )
    (net (code "61") (name "Net-(IC2-L10)") (class "Default")
      (node (ref "IC2") (pin "17") (pinfunction "L10_17") (pintype "output"))
      (node (ref "R10") (pin "2") (pinfunction "2_2") (pintype "passive"))
    )
    (net (code "62") (name "Net-(IC2-L11)") (class "Default")
      (node (ref "IC2") (pin "18") (pinfunction "L11_18") (pintype "output"))
      (node (ref "R9") (pin "2") (pinfunction "2_2") (pintype "passive"))
    )
    (net (code "63") (name "Net-(IC2-L12)") (class "Default")
      (node (ref "IC2") (pin "19") (pinfunction "L12_19") (pintype "output"))
      (node (ref "R8") (pin "2") (pinfunction "2_2") (pintype "passive"))
    )
    (net (code "64") (name "Net-(IC2-L13)") (class "Default")
      (node (ref "IC2") (pin "20") (pinfunction "L13_20") (pintype "output"))
      (node (ref "R7") (pin "2") (pinfunction "2_2") (pintype "passive"))
    )
    (net (code "65") (name "Net-(IC2-L14)") (class "Default")
      (node (ref "IC2") (pin "21") (pinfunction "L14_21") (pintype "output"))
      (node (ref "R6") (pin "2") (pinfunction "2_2") (pintype "passive"))
    )
    (net (code "66") (name "Net-(IC2-L15)") (class "Default")
      (node (ref "IC2") (pin "22") (pinfunction "L15_22") (pintype "output"))
      (node (ref "R5") (pin "2") (pinfunction "2_2") (pintype "passive"))
    )
    (net (code "67") (name "Net-(IC3-L0)") (class "Default")
      (node (ref "IC3") (pin "6") (pinfunction "L0_6") (pintype "output"))
      (node (ref "R32") (pin "2") (pinfunction "2_2") (pintype "passive"))
    )
    (net (code "68") (name "Net-(IC3-L1)") (class "Default")
      (node (ref "IC3") (pin "7") (pinfunction "L1_7") (pintype "output"))
      (node (ref "R31") (pin "2") (pinfunction "2_2") (pintype "passive"))
    )
    (net (code "69") (name "SDI_MOSI") (class "Default")
      (node (ref "SERIAL") (pin "8") (pinfunction "8_8") (pintype "passive"))
      (node (ref "SSW1") (pin "6") (pinfunction "SDI_6") (pintype "bidirectional"))
      (node (ref "SSW2") (pin "6") (pinfunction "SDI_6") (pintype "bidirectional"))
      (node (ref "SSW5") (pin "6") (pinfunction "SDI_6") (pintype "bidirectional"))
      (node (ref "SSW5ALT") (pin "6") (pinfunction "SDI_6") (pintype "bidirectional"))
      (node (ref "SSW6") (pin "6") (pinfunction "SDI_6") (pintype "bidirectional"))
      (node (ref "SSW6ALT") (pin "6") (pinfunction "SDI_6") (pintype "bidirectional"))
    )
    (net (code "70") (name "SDI_SCLK") (class "Default")
      (node (ref "SERIAL") (pin "7") (pinfunction "7_7") (pintype "passive"))
      (node (ref "SSW1") (pin "7") (pinfunction "SCK_7") (pintype "bidirectional"))
      (node (ref "SSW2") (pin "7") (pinfunction "SCK_7") (pintype "bidirectional"))
      (node (ref "SSW5") (pin "7") (pinfunction "SCK_7") (pintype "bidirectional"))
      (node (ref "SSW5ALT") (pin "7") (pinfunction "SCK_7") (pintype "bidirectional"))
      (node (ref "SSW6") (pin "7") (pinfunction "SCK_7") (pintype "bidirectional"))
      (node (ref "SSW6ALT") (pin "7") (pinfunction "SCK_7") (pintype "bidirectional"))
    )
    (net (code "71") (name "SLIDER_IN") (class "Default")
      (node (ref "C6") (pin "1") (pinfunction "1_1") (pintype "passive"))
      (node (ref "JP1") (pin "2") (pinfunction "2_2") (pintype "passive"))
      (node (ref "JP2") (pin "2") (pinfunction "2_2") (pintype "passive"))
      (node (ref "POT1") (pin "2A") (pinfunction "S_2A") (pintype "passive"))
      (node (ref "POT1ALT") (pin "2A") (pinfunction "S_2A") (pintype "passive"))
      (node (ref "SERIAL") (pin "5") (pinfunction "5_5") (pintype "passive"))
    )
    (net (code "72") (name "unconnected-(IC1-GPB0-Pad1)") (class "Default")
      (node (ref "IC1") (pin "1") (pinfunction "GPB0_1") (pintype "bidirectional"))
    )
    (net (code "73") (name "unconnected-(IC1-GPB1-Pad2)") (class "Default")
      (node (ref "IC1") (pin "2") (pinfunction "GPB1_2") (pintype "bidirectional"))
    )
    (net (code "74") (name "unconnected-(IC1-GPB2-Pad3)") (class "Default")
      (node (ref "IC1") (pin "3") (pinfunction "GPB2_3") (pintype "bidirectional"))
    )
    (net (code "75") (name "unconnected-(IC1-GPB3-Pad4)") (class "Default")
      (node (ref "IC1") (pin "4") (pinfunction "GPB3_4") (pintype "bidirectional"))
    )
    (net (code "76") (name "unconnected-(IC1-GPB5-Pad6)") (class "Default")
      (node (ref "IC1") (pin "6") (pinfunction "GPB5_6") (pintype "bidirectional"))
    )
    (net (code "77") (name "unconnected-(IC1-GPB6-Pad7)") (class "Default")
      (node (ref "IC1") (pin "7") (pinfunction "GPB6_7") (pintype "bidirectional"))
    )
    (net (code "78") (name "unconnected-(IC1-GPB7-Pad8)") (class "Default")
      (node (ref "IC1") (pin "8") (pinfunction "GPB7_8") (pintype "bidirectional"))
    )
    (net (code "79") (name "unconnected-(IC1-INTA-Pad20)") (class "Default")
      (node (ref "IC1") (pin "20") (pinfunction "INTA_20") (pintype "output"))
    )
    (net (code "80") (name "unconnected-(IC1-INTB-Pad19)") (class "Default")
      (node (ref "IC1") (pin "19") (pinfunction "INTB_19") (pintype "output"))
    )
    (net (code "81") (name "unconnected-(IC3-L2-Pad8)") (class "Default")
      (node (ref "IC3") (pin "8") (pinfunction "L2_8") (pintype "output"))
    )
    (net (code "82") (name "unconnected-(IC3-L3-Pad9)") (class "Default")
      (node (ref "IC3") (pin "9") (pinfunction "L3_9") (pintype "output"))
    )
    (net (code "83") (name "unconnected-(IC3-L4-Pad10)") (class "Default")
      (node (ref "IC3") (pin "10") (pinfunction "L4_10") (pintype "output"))
    )
    (net (code "84") (name "unconnected-(IC3-L5-Pad11)") (class "Default")
      (node (ref "IC3") (pin "11") (pinfunction "L5_11") (pintype "output"))
    )
    (net (code "85") (name "unconnected-(IC3-L6-Pad12)") (class "Default")
      (node (ref "IC3") (pin "12") (pinfunction "L6_12") (pintype "output"))
    )
    (net (code "86") (name "unconnected-(IC3-L7-Pad13)") (class "Default")
      (node (ref "IC3") (pin "13") (pinfunction "L7_13") (pintype "output"))
    )
    (net (code "87") (name "unconnected-(IC3-L8-Pad15)") (class "Default")
      (node (ref "IC3") (pin "15") (pinfunction "L8_15") (pintype "output"))
    )
    (net (code "88") (name "unconnected-(IC3-L9-Pad16)") (class "Default")
      (node (ref "IC3") (pin "16") (pinfunction "L9_16") (pintype "output"))
    )
    (net (code "89") (name "unconnected-(IC3-L10-Pad17)") (class "Default")
      (node (ref "IC3") (pin "17") (pinfunction "L10_17") (pintype "output"))
    )
    (net (code "90") (name "unconnected-(IC3-L11-Pad18)") (class "Default")
      (node (ref "IC3") (pin "18") (pinfunction "L11_18") (pintype "output"))
    )
    (net (code "91") (name "unconnected-(IC3-L12-Pad19)") (class "Default")
      (node (ref "IC3") (pin "19") (pinfunction "L12_19") (pintype "output"))
    )
    (net (code "92") (name "unconnected-(IC3-L13-Pad20)") (class "Default")
      (node (ref "IC3") (pin "20") (pinfunction "L13_20") (pintype "output"))
    )
    (net (code "93") (name "unconnected-(IC3-L14-Pad21)") (class "Default")
      (node (ref "IC3") (pin "21") (pinfunction "L14_21") (pintype "output"))
    )
    (net (code "94") (name "unconnected-(IC3-L15-Pad22)") (class "Default")
      (node (ref "IC3") (pin "22") (pinfunction "L15_22") (pintype "output"))
    )
    (net (code "95") (name "unconnected-(IC5-INTA-Pad20)") (class "Default")
      (node (ref "IC5") (pin "20") (pinfunction "INTA_20") (pintype "output"))
    )
    (net (code "96") (name "unconnected-(IC5-INTB-Pad19)") (class "Default")
      (node (ref "IC5") (pin "19") (pinfunction "INTB_19") (pintype "output"))
    )
    (net (code "97") (name "unconnected-(SSW1-SDO-Pad5)") (class "Default")
      (node (ref "SSW1") (pin "5") (pinfunction "SDO_5") (pintype "bidirectional"))
    )
    (net (code "98") (name "unconnected-(SSW2-SDO-Pad5)") (class "Default")
      (node (ref "SSW2") (pin "5") (pinfunction "SDO_5") (pintype "bidirectional"))
    )
    (net (code "99") (name "unconnected-(SSW5-SDO-Pad5)") (class "Default")
      (node (ref "SSW5") (pin "5") (pinfunction "SDO_5") (pintype "bidirectional"))
    )
    (net (code "100") (name "unconnected-(SSW5ALT-SDO-Pad5)") (class "Default")
      (node (ref "SSW5ALT") (pin "5") (pinfunction "SDO_5") (pintype "bidirectional"))
    )
    (net (code "101") (name "unconnected-(SSW6-SDO-Pad5)") (class "Default")
      (node (ref "SSW6") (pin "5") (pinfunction "SDO_5") (pintype "bidirectional"))
    )
    (net (code "102") (name "unconnected-(SSW6ALT-SDO-Pad5)") (class "Default")
      (node (ref "SSW6ALT") (pin "5") (pinfunction "SDO_5") (pintype "bidirectional"))
    )
  )
)
